# EIT_Teensy_Teensy3_6.net
KiCad netlist of a schematic drawn in Altium Designer
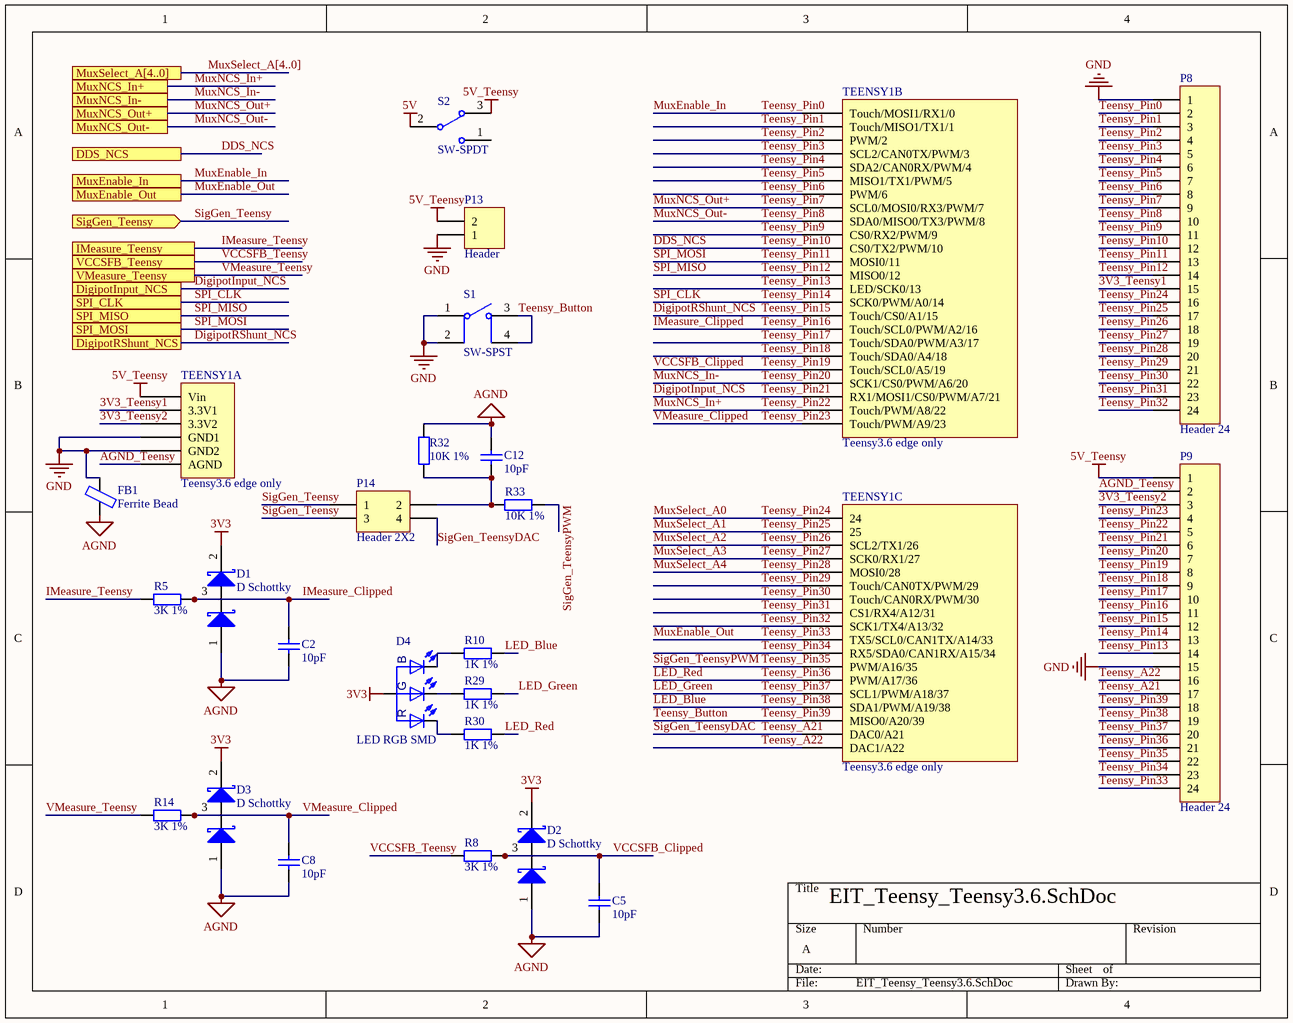
[diagram p0: EIT_Teensy_Teensy3.6.SchDoc]

(export (version "E")
  (design (tool "Eeschema 10.0.6"))
  (components
    (comp (ref "C2")
      (value "10pF")
      (footprint "0603 CAP")
      (fields
        (field (name "MANUFACTURER") "Yageo")
        (field (name "MANUFACTURER PART NUMBER") "CC0603JRNPO9BN100")
        (field (name "TOLERANCE") "5%")
      )
      (libsource (lib "EitLib") (part "Cap 0603 10pF 5% 100V"))
    )
    (comp (ref "C5")
      (value "10pF")
      (footprint "0603 CAP")
      (fields
        (field (name "MANUFACTURER") "Yageo")
        (field (name "MANUFACTURER PART NUMBER") "CC0603JRNPO9BN100")
        (field (name "TOLERANCE") "5%")
      )
      (libsource (lib "EitLib") (part "Cap 0603 10pF 5% 100V"))
    )
    (comp (ref "C8")
      (value "10pF")
      (footprint "0603 CAP")
      (fields
        (field (name "MANUFACTURER") "Yageo")
        (field (name "MANUFACTURER PART NUMBER") "CC0603JRNPO9BN100")
        (field (name "TOLERANCE") "5%")
      )
      (libsource (lib "EitLib") (part "Cap 0603 10pF 5% 100V"))
    )
    (comp (ref "C12")
      (value "10pF")
      (footprint "0603 CAP")
      (fields
        (field (name "MANUFACTURER") "Yageo")
        (field (name "MANUFACTURER PART NUMBER") "CC0603JRNPO9BN100")
        (field (name "TOLERANCE") "5%")
      )
      (libsource (lib "EitLib") (part "Cap 0603 10pF 5% 100V"))
    )
    (comp (ref "D1")
      (value "D Schottky")
      (footprint "SOT-23_STM-M")
      (description "Rectifier Diode Small Signal Schottky 40V 0.3A 5ns 3-Pin SOT-23 T/R")
      (fields
        (field (name "MANUFACTURER") "STMicroelectronics")
        (field (name "MANUFACTURER PART NUMBER") "BAT54SFILM")
      )
      (libsource (lib "EitLib") (part "Diode Array Schottky BAT54S SOT23-3"))
    )
    (comp (ref "D2")
      (value "D Schottky")
      (footprint "SOT-23_STM-M")
      (description "Rectifier Diode Small Signal Schottky 40V 0.3A 5ns 3-Pin SOT-23 T/R")
      (fields
        (field (name "MANUFACTURER") "STMicroelectronics")
        (field (name "MANUFACTURER PART NUMBER") "BAT54SFILM")
      )
      (libsource (lib "EitLib") (part "Diode Array Schottky BAT54S SOT23-3"))
    )
    (comp (ref "D3")
      (value "D Schottky")
      (footprint "SOT-23_STM-M")
      (description "Rectifier Diode Small Signal Schottky 40V 0.3A 5ns 3-Pin SOT-23 T/R")
      (fields
        (field (name "MANUFACTURER") "STMicroelectronics")
        (field (name "MANUFACTURER PART NUMBER") "BAT54SFILM")
      )
      (libsource (lib "EitLib") (part "Diode Array Schottky BAT54S SOT23-3"))
    )
    (comp (ref "D4")
      (value "LED RGB SMD")
      (footprint "LED_RGB")
      (description "LED RGB DIFFUSED SMD")
      (fields
        (field (name "MANUFACTURER") "Wurth Electronics")
        (field (name "MANUFACTURER PART NUMBER") "150066M153000")
      )
      (libsource (lib "EitLib") (part "LED RGB SMD"))
    )
    (comp (ref "FB1")
      (value "Ferrite Bead")
      (footprint "0603 CAP")
      (fields
        (field (name "MANUFACTURER") "Wurth Electronics")
        (field (name "MANUFACTURER PART NUMBER") "742792651")
        (field (name "TOLERANCE") "25%")
      )
      (libsource (lib "EitLib") (part "Ferrite Bead 0603 600R"))
    )
    (comp (ref "P8")
      (value "Header 24")
      (footprint "HDR1X24")
      (description "CONN HEADER .100 SNGL STR 24POS")
      (fields
        (field (name "MANUFACTURER") "Sullins")
        (field (name "MANUFACTURER PART NUMBER") "PRPC024SFAN-RC")
      )
      (libsource (lib "EitLib") (part "Header 24x1 Male"))
    )
    (comp (ref "P9")
      (value "Header 24")
      (footprint "HDR1X24")
      (description "CONN HEADER .100 SNGL STR 24POS")
      (fields
        (field (name "MANUFACTURER") "Sullins")
        (field (name "MANUFACTURER PART NUMBER") "PRPC024SFAN-RC")
      )
      (libsource (lib "EitLib") (part "Header 24x1 Male"))
    )
    (comp (ref "P13")
      (value "Header")
      (footprint "HEADER 2.54MM 2X1 MALE")
      (description "CONN HEADER VERT 2POS 2.54MM")
      (fields
        (field (name "MANUFACTURER") "Sullins")
        (field (name "MANUFACTURER PART NUMBER") "PRPC002SAAN-RC")
      )
      (libsource (lib "EitLib") (part "Header 2x1 2.54mm T/H Male"))
    )
    (comp (ref "P14")
      (value "Header 2X2")
      (footprint "HDR2X2 Male 2.54mm")
      (description "Header, 2-Pin, Dual row")
      (libsource (lib "EitLib") (part "Header 2X2 2.54mm Male"))
    )
    (comp (ref "R5")
      (value "3K 1%")
      (footprint "0603 RES")
      (description "Res Thick Film 0603 3K Ohm 1% 0.1W(1/10W) ±100ppm/C Pad SMD T/R")
      (fields
        (field (name "MANUFACTURER") "Yageo")
        (field (name "MANUFACTURER PART NUMBER") "RC0603FR-073KL")
      )
      (libsource (lib "EitLib") (part "Res 0603 3K 1%"))
    )
    (comp (ref "R8")
      (value "3K 1%")
      (footprint "0603 RES")
      (description "Res Thick Film 0603 3K Ohm 1% 0.1W(1/10W) ±100ppm/C Pad SMD T/R")
      (fields
        (field (name "MANUFACTURER") "Yageo")
        (field (name "MANUFACTURER PART NUMBER") "RC0603FR-073KL")
      )
      (libsource (lib "EitLib") (part "Res 0603 3K 1%"))
    )
    (comp (ref "R10")
      (value "1K 1%")
      (footprint "0603 RES")
      (description "RES SMD 1K OHM 1% 1/10W 0603")
      (fields
        (field (name "MANUFACTURER") "Yageo")
        (field (name "MANUFACTURER PART NUMBER") "RC0603FR-071KL")
      )
      (libsource (lib "EitLib") (part "Res 0603 1K 1%"))
    )
    (comp (ref "R14")
      (value "3K 1%")
      (footprint "0603 RES")
      (description "Res Thick Film 0603 3K Ohm 1% 0.1W(1/10W) ±100ppm/C Pad SMD T/R")
      (fields
        (field (name "MANUFACTURER") "Yageo")
        (field (name "MANUFACTURER PART NUMBER") "RC0603FR-073KL")
      )
      (libsource (lib "EitLib") (part "Res 0603 3K 1%"))
    )
    (comp (ref "R29")
      (value "1K 1%")
      (footprint "0603 RES")
      (description "RES SMD 1K OHM 1% 1/10W 0603")
      (fields
        (field (name "MANUFACTURER") "Yageo")
        (field (name "MANUFACTURER PART NUMBER") "RC0603FR-071KL")
      )
      (libsource (lib "EitLib") (part "Res 0603 1K 1%"))
    )
    (comp (ref "R30")
      (value "1K 1%")
      (footprint "0603 RES")
      (description "RES SMD 1K OHM 1% 1/10W 0603")
      (fields
        (field (name "MANUFACTURER") "Yageo")
        (field (name "MANUFACTURER PART NUMBER") "RC0603FR-071KL")
      )
      (libsource (lib "EitLib") (part "Res 0603 1K 1%"))
    )
    (comp (ref "R32")
      (value "10K 1%")
      (footprint "0603 RES")
      (description "Res General Purpose Thick Film 0603 10K Ohm 1% 1/10W ±100ppm/°C Molded SMD Paper T/R")
      (fields
        (field (name "MANUFACTURER") "Yageo")
        (field (name "MANUFACTURER PART NUMBER") "RC0603FR-0710KL")
      )
      (libsource (lib "") (part "Res 0603 10K 1%_1"))
    )
    (comp (ref "R33")
      (value "10K 1%")
      (footprint "0603 RES")
      (description "Res General Purpose Thick Film 0603 10K Ohm 1% 1/10W ±100ppm/°C Molded SMD Paper T/R")
      (fields
        (field (name "MANUFACTURER") "Yageo")
        (field (name "MANUFACTURER PART NUMBER") "RC0603FR-0710KL")
      )
      (libsource (lib "EitLib") (part "Res 0603 10K 1%"))
    )
    (comp (ref "S1")
      (value "SW-SPST")
      (footprint "Tactile Switch SMD MOM")
      (description "Switch Tactile N.O. SPST Round Button Gull Wing 0.05A 12VDC 2.55N SMD T/R")
      (fields
        (field (name "MANUFACTURER") "E-Switch")
        (field (name "MANUFACTURER PART NUMBER") "TL3305BF260QG")
      )
      (libsource (lib "EitLib") (part "Switch Tactile SMD MOM-NO 50mA"))
    )
    (comp (ref "S2")
      (value "SW-SPDT")
      (footprint "Switch Slide SPDT")
      (description "SWITCH SLIDE SPDT 300MA 125V")
      (fields
        (field (name "MANUFACTURER") "TE Connectivity Alcoswitch")
        (field (name "MANUFACTURER PART NUMBER") "1825255-1")
      )
      (libsource (lib "EitLib") (part "Switch Slide SPDT T/H"))
    )
    (comp (ref "TEENSY1")
      (value "Teensy3.6 edge only")
      (footprint "Teensy3.6-edgeonly")
      (libsource (lib "EitLib") (part "Teensy3.6 edge only"))
    )
  )
  (nets
    (net (code "1") (name "/3V3_Teensy1") (class "Default")
      (node (ref "P8") (pin "15") (pinfunction "15_15") (pintype "passive"))
      (node (ref "TEENSY1") (pin "3.3V1") (pinfunction "3.3V1_3.3V1") (pintype "power_in"))
    )
    (net (code "2") (name "/3V3_Teensy2") (class "Default")
      (node (ref "P9") (pin "3") (pinfunction "3_3") (pintype "passive"))
      (node (ref "TEENSY1") (pin "3.3V2") (pinfunction "3.3V2_3.3V2") (pintype "power_in"))
    )
    (net (code "3") (name "/AGND_Teensy") (class "Default")
      (node (ref "P9") (pin "2") (pinfunction "2_2") (pintype "passive"))
      (node (ref "TEENSY1") (pin "AGND") (pinfunction "AGND_AGND") (pintype "power_in"))
    )
    (net (code "4") (name "/DDS_NCS") (class "Default")
      (node (ref "P8") (pin "12") (pinfunction "12_12") (pintype "passive"))
      (node (ref "TEENSY1") (pin "10") (pinfunction "CS0/TX2/PWM/10_10") (pintype "passive"))
    )
    (net (code "5") (name "/DigipotInput_NCS") (class "Default")
      (node (ref "P9") (pin "6") (pinfunction "6_6") (pintype "passive"))
      (node (ref "TEENSY1") (pin "21") (pinfunction "RX1/MOSI1/CS0/PWM/A7/21_21") (pintype "passive"))
    )
    (net (code "6") (name "/DigipotRShunt_NCS") (class "Default")
      (node (ref "P9") (pin "12") (pinfunction "12_12") (pintype "passive"))
      (node (ref "TEENSY1") (pin "15") (pinfunction "Touch/CS0/A1/15_15") (pintype "passive"))
    )
    (net (code "7") (name "/IMeasure_Clipped") (class "Default")
      (node (ref "C2") (pin "1") (pinfunction "1_1") (pintype "passive"))
      (node (ref "D1") (pin "3") (pinfunction "C_3") (pintype "passive"))
      (node (ref "P9") (pin "11") (pinfunction "11_11") (pintype "passive"))
      (node (ref "R5") (pin "2") (pinfunction "2_2") (pintype "passive"))
      (node (ref "TEENSY1") (pin "16") (pinfunction "Touch/SCL0/PWM/A2/16_16") (pintype "passive"))
    )
    (net (code "8") (name "/IMeasure_Teensy") (class "Default")
      (node (ref "R5") (pin "1") (pinfunction "1_1") (pintype "passive"))
    )
    (net (code "9") (name "/LED_Blue") (class "Default")
      (node (ref "P9") (pin "19") (pinfunction "19_19") (pintype "passive"))
      (node (ref "R10") (pin "1") (pinfunction "1_1") (pintype "passive"))
      (node (ref "TEENSY1") (pin "38") (pinfunction "SDA1/PWM/A19/38_38") (pintype "passive"))
    )
    (net (code "10") (name "/LED_Green") (class "Default")
      (node (ref "P9") (pin "20") (pinfunction "20_20") (pintype "passive"))
      (node (ref "R29") (pin "1") (pinfunction "1_1") (pintype "passive"))
      (node (ref "TEENSY1") (pin "37") (pinfunction "SCL1/PWM/A18/37_37") (pintype "passive"))
    )
    (net (code "11") (name "/LED_Red") (class "Default")
      (node (ref "P9") (pin "21") (pinfunction "21_21") (pintype "passive"))
      (node (ref "R30") (pin "1") (pinfunction "1_1") (pintype "passive"))
      (node (ref "TEENSY1") (pin "36") (pinfunction "PWM/A17/36_36") (pintype "passive"))
    )
    (net (code "12") (name "/MuxEnable_In") (class "Default")
      (node (ref "P8") (pin "2") (pinfunction "2_2") (pintype "passive"))
      (node (ref "TEENSY1") (pin "0") (pinfunction "Touch/MOSI1/RX1/0_0") (pintype "passive"))
    )
    (net (code "13") (name "/MuxEnable_Out") (class "Default")
      (node (ref "P9") (pin "24") (pinfunction "24_24") (pintype "passive"))
      (node (ref "TEENSY1") (pin "33") (pinfunction "TX5/SCL0/CAN1TX/A14/33_33") (pintype "passive"))
    )
    (net (code "14") (name "/MuxNCS_In+") (class "Default")
      (node (ref "P9") (pin "5") (pinfunction "5_5") (pintype "passive"))
      (node (ref "TEENSY1") (pin "22") (pinfunction "Touch/PWM/A8/22_22") (pintype "passive"))
    )
    (net (code "15") (name "/MuxNCS_In-") (class "Default")
      (node (ref "P9") (pin "7") (pinfunction "7_7") (pintype "passive"))
      (node (ref "TEENSY1") (pin "20") (pinfunction "SCK1/CS0/PWM/A6/20_20") (pintype "passive"))
    )
    (net (code "16") (name "/MuxNCS_Out+") (class "Default")
      (node (ref "P8") (pin "9") (pinfunction "9_9") (pintype "passive"))
      (node (ref "TEENSY1") (pin "7") (pinfunction "SCL0/MOSI0/RX3/PWM/7_7") (pintype "passive"))
    )
    (net (code "17") (name "/MuxNCS_Out-") (class "Default")
      (node (ref "P8") (pin "10") (pinfunction "10_10") (pintype "passive"))
      (node (ref "TEENSY1") (pin "8") (pinfunction "SDA0/MISO0/TX3/PWM/8_8") (pintype "passive"))
    )
    (net (code "18") (name "/MuxSelect_A0") (class "Default")
      (node (ref "P8") (pin "16") (pinfunction "16_16") (pintype "passive"))
      (node (ref "TEENSY1") (pin "24") (pinfunction "24_24") (pintype "passive"))
    )
    (net (code "19") (name "/MuxSelect_A1") (class "Default")
      (node (ref "P8") (pin "17") (pinfunction "17_17") (pintype "passive"))
      (node (ref "TEENSY1") (pin "25") (pinfunction "25_25") (pintype "passive"))
    )
    (net (code "20") (name "/MuxSelect_A2") (class "Default")
      (node (ref "P8") (pin "18") (pinfunction "18_18") (pintype "passive"))
      (node (ref "TEENSY1") (pin "26") (pinfunction "SCL2/TX1/26_26") (pintype "passive"))
    )
    (net (code "21") (name "/MuxSelect_A3") (class "Default")
      (node (ref "P8") (pin "19") (pinfunction "19_19") (pintype "passive"))
      (node (ref "TEENSY1") (pin "27") (pinfunction "SCK0/RX1/27_27") (pintype "passive"))
    )
    (net (code "22") (name "/MuxSelect_A4") (class "Default")
      (node (ref "P8") (pin "20") (pinfunction "20_20") (pintype "passive"))
      (node (ref "TEENSY1") (pin "28") (pinfunction "MOSI0/28_28") (pintype "passive"))
    )
    (net (code "24") (name "/SPI_CLK") (class "Default")
      (node (ref "P9") (pin "13") (pinfunction "13_13") (pintype "passive"))
      (node (ref "TEENSY1") (pin "14") (pinfunction "SCK0/PWM/A0/14_14") (pintype "passive"))
    )
    (net (code "25") (name "/SPI_MISO") (class "Default")
      (node (ref "P8") (pin "14") (pinfunction "14_14") (pintype "passive"))
      (node (ref "TEENSY1") (pin "12") (pinfunction "MISO0/12_12") (pintype "passive"))
    )
    (net (code "26") (name "/SPI_MOSI") (class "Default")
      (node (ref "P8") (pin "13") (pinfunction "13_13") (pintype "passive"))
      (node (ref "TEENSY1") (pin "11") (pinfunction "MOSI0/11_11") (pintype "passive"))
    )
    (net (code "27") (name "/SigGen_Teensy") (class "Default")
      (node (ref "P14") (pin "1") (pinfunction "1_1") (pintype "passive"))
      (node (ref "P14") (pin "3") (pinfunction "3_3") (pintype "passive"))
    )
    (net (code "28") (name "/SigGen_TeensyDAC") (class "Default")
      (node (ref "P14") (pin "4") (pinfunction "4_4") (pintype "passive"))
      (node (ref "P9") (pin "17") (pinfunction "17_17") (pintype "passive"))
      (node (ref "TEENSY1") (pin "A21") (pinfunction "DAC0/A21_A21") (pintype "passive"))
    )
    (net (code "29") (name "/SigGen_TeensyPWM") (class "Default")
      (node (ref "P9") (pin "22") (pinfunction "22_22") (pintype "passive"))
      (node (ref "R33") (pin "1") (pinfunction "1_1") (pintype "passive"))
      (node (ref "TEENSY1") (pin "35") (pinfunction "PWM/A16/35_35") (pintype "passive"))
    )
    (net (code "30") (name "/Teensy_A22") (class "Default")
      (node (ref "P9") (pin "16") (pinfunction "16_16") (pintype "passive"))
      (node (ref "TEENSY1") (pin "A22") (pinfunction "DAC1/A22_A22") (pintype "passive"))
    )
    (net (code "31") (name "/Teensy_Button") (class "Default")
      (node (ref "P9") (pin "18") (pinfunction "18_18") (pintype "passive"))
      (node (ref "S1") (pin "3") (pinfunction "COMMON_3") (pintype "passive"))
      (node (ref "S1") (pin "4") (pinfunction "NO_4") (pintype "passive"))
      (node (ref "TEENSY1") (pin "39") (pinfunction "MISO0/A20/39_39") (pintype "passive"))
    )
    (net (code "32") (name "/Teensy_Pin1") (class "Default")
      (node (ref "P8") (pin "3") (pinfunction "3_3") (pintype "passive"))
      (node (ref "TEENSY1") (pin "1") (pinfunction "Touch/MISO1/TX1/1_1") (pintype "passive"))
    )
    (net (code "33") (name "/Teensy_Pin2") (class "Default")
      (node (ref "P8") (pin "4") (pinfunction "4_4") (pintype "passive"))
      (node (ref "TEENSY1") (pin "2") (pinfunction "PWM/2_2") (pintype "passive"))
    )
    (net (code "34") (name "/Teensy_Pin3") (class "Default")
      (node (ref "P8") (pin "5") (pinfunction "5_5") (pintype "passive"))
      (node (ref "TEENSY1") (pin "3") (pinfunction "SCL2/CAN0TX/PWM/3_3") (pintype "passive"))
    )
    (net (code "35") (name "/Teensy_Pin4") (class "Default")
      (node (ref "P8") (pin "6") (pinfunction "6_6") (pintype "passive"))
      (node (ref "TEENSY1") (pin "4") (pinfunction "SDA2/CAN0RX/PWM/4_4") (pintype "passive"))
    )
    (net (code "36") (name "/Teensy_Pin5") (class "Default")
      (node (ref "P8") (pin "7") (pinfunction "7_7") (pintype "passive"))
      (node (ref "TEENSY1") (pin "5") (pinfunction "MISO1/TX1/PWM/5_5") (pintype "passive"))
    )
    (net (code "37") (name "/Teensy_Pin6") (class "Default")
      (node (ref "P8") (pin "8") (pinfunction "8_8") (pintype "passive"))
      (node (ref "TEENSY1") (pin "6") (pinfunction "PWM/6_6") (pintype "passive"))
    )
    (net (code "38") (name "/Teensy_Pin9") (class "Default")
      (node (ref "P8") (pin "11") (pinfunction "11_11") (pintype "passive"))
      (node (ref "TEENSY1") (pin "9") (pinfunction "CS0/RX2/PWM/9_9") (pintype "passive"))
    )
    (net (code "39") (name "/Teensy_Pin13") (class "Default")
      (node (ref "P9") (pin "14") (pinfunction "14_14") (pintype "passive"))
      (node (ref "TEENSY1") (pin "13") (pinfunction "LED/SCK0/13_13") (pintype "passive"))
    )
    (net (code "40") (name "/Teensy_Pin17") (class "Default")
      (node (ref "P9") (pin "10") (pinfunction "10_10") (pintype "passive"))
      (node (ref "TEENSY1") (pin "17") (pinfunction "Touch/SDA0/PWM/A3/17_17") (pintype "passive"))
    )
    (net (code "41") (name "/Teensy_Pin18") (class "Default")
      (node (ref "P9") (pin "9") (pinfunction "9_9") (pintype "passive"))
      (node (ref "TEENSY1") (pin "18") (pinfunction "Touch/SDA0/A4/18_18") (pintype "passive"))
    )
    (net (code "42") (name "/Teensy_Pin19") (class "Default")
      (node (ref "C5") (pin "1") (pinfunction "1_1") (pintype "passive"))
      (node (ref "D2") (pin "3") (pinfunction "C_3") (pintype "passive"))
      (node (ref "P9") (pin "8") (pinfunction "8_8") (pintype "passive"))
      (node (ref "R8") (pin "2") (pinfunction "2_2") (pintype "passive"))
      (node (ref "TEENSY1") (pin "19") (pinfunction "Touch/SCL0/A5/19_19") (pintype "passive"))
    )
    (net (code "43") (name "/Teensy_Pin23") (class "Default")
      (node (ref "C8") (pin "1") (pinfunction "1_1") (pintype "passive"))
      (node (ref "D3") (pin "3") (pinfunction "C_3") (pintype "passive"))
      (node (ref "P9") (pin "4") (pinfunction "4_4") (pintype "passive"))
      (node (ref "R14") (pin "2") (pinfunction "2_2") (pintype "passive"))
      (node (ref "TEENSY1") (pin "23") (pinfunction "Touch/PWM/A9/23_23") (pintype "passive"))
    )
    (net (code "44") (name "/Teensy_Pin29") (class "Default")
      (node (ref "P8") (pin "21") (pinfunction "21_21") (pintype "passive"))
      (node (ref "TEENSY1") (pin "29") (pinfunction "Touch/CAN0TX/PWM/29_29") (pintype "passive"))
    )
    (net (code "45") (name "/Teensy_Pin30") (class "Default")
      (node (ref "P8") (pin "22") (pinfunction "22_22") (pintype "passive"))
      (node (ref "TEENSY1") (pin "30") (pinfunction "Touch/CAN0RX/PWM/30_30") (pintype "passive"))
    )
    (net (code "46") (name "/Teensy_Pin31") (class "Default")
      (node (ref "P8") (pin "23") (pinfunction "23_23") (pintype "passive"))
      (node (ref "TEENSY1") (pin "31") (pinfunction "CS1/RX4/A12/31_31") (pintype "passive"))
    )
    (net (code "47") (name "/Teensy_Pin32") (class "Default")
      (node (ref "P8") (pin "24") (pinfunction "24_24") (pintype "passive"))
      (node (ref "TEENSY1") (pin "32") (pinfunction "SCK1/TX4/A13/32_32") (pintype "passive"))
    )
    (net (code "48") (name "/Teensy_Pin34") (class "Default")
      (node (ref "P9") (pin "23") (pinfunction "23_23") (pintype "passive"))
      (node (ref "TEENSY1") (pin "34") (pinfunction "RX5/SDA0/CAN1RX/A15/34_34") (pintype "passive"))
    )
    (net (code "49") (name "/VCCSFB_Teensy") (class "Default")
      (node (ref "R8") (pin "1") (pinfunction "1_1") (pintype "passive"))
    )
    (net (code "50") (name "/VMeasure_Teensy") (class "Default")
      (node (ref "R14") (pin "1") (pinfunction "1_1") (pintype "passive"))
    )
    (net (code "51") (name "3V3") (class "Default")
      (node (ref "D1") (pin "2") (pinfunction "K_2") (pintype "passive"))
      (node (ref "D2") (pin "2") (pinfunction "K_2") (pintype "passive"))
      (node (ref "D3") (pin "2") (pinfunction "K_2") (pintype "passive"))
      (node (ref "D4") (pin "4") (pinfunction "CA_4") (pintype "passive"))
    )
    (net (code "52") (name "5V") (class "Default")
      (node (ref "S2") (pin "2") (pinfunction "2_2") (pintype "passive"))
    )
    (net (code "53") (name "5V_Teensy") (class "Default")
      (node (ref "P13") (pin "2") (pinfunction "2_2") (pintype "passive"))
      (node (ref "P9") (pin "1") (pinfunction "1_1") (pintype "passive"))
      (node (ref "S2") (pin "3") (pinfunction "3_3") (pintype "passive"))
      (node (ref "TEENSY1") (pin "VIN") (pinfunction "Vin_VIN") (pintype "power_in"))
    )
    (net (code "54") (name "AGND") (class "Default")
      (node (ref "C12") (pin "1") (pinfunction "1_1") (pintype "passive"))
      (node (ref "C2") (pin "2") (pinfunction "2_2") (pintype "passive"))
      (node (ref "C5") (pin "2") (pinfunction "2_2") (pintype "passive"))
      (node (ref "C8") (pin "2") (pinfunction "2_2") (pintype "passive"))
      (node (ref "D1") (pin "1") (pinfunction "A_1") (pintype "passive"))
      (node (ref "D2") (pin "1") (pinfunction "A_1") (pintype "passive"))
      (node (ref "D3") (pin "1") (pinfunction "A_1") (pintype "passive"))
      (node (ref "FB1") (pin "1") (pinfunction "1_1") (pintype "passive"))
      (node (ref "R32") (pin "2") (pinfunction "2_2") (pintype "passive"))
    )
    (net (code "55") (name "GND") (class "Default")
      (node (ref "FB1") (pin "2") (pinfunction "2_2") (pintype "passive"))
      (node (ref "P13") (pin "1") (pinfunction "1_1") (pintype "passive"))
      (node (ref "P8") (pin "1") (pinfunction "1_1") (pintype "passive"))
      (node (ref "P9") (pin "15") (pinfunction "15_15") (pintype "passive"))
      (node (ref "S1") (pin "1") (pinfunction "COMMON_1") (pintype "passive"))
      (node (ref "S1") (pin "2") (pinfunction "NO_2") (pintype "passive"))
      (node (ref "TEENSY1") (pin "GND1") (pinfunction "GND1_GND1") (pintype "power_in"))
      (node (ref "TEENSY1") (pin "GND2") (pinfunction "GND2_GND2") (pintype "power_in"))
    )
    (net (code "56") (name "Net-(C12-Pad2)") (class "Default")
      (node (ref "C12") (pin "2") (pinfunction "2_2") (pintype "passive"))
      (node (ref "P14") (pin "2") (pinfunction "2_2") (pintype "passive"))
      (node (ref "R32") (pin "1") (pinfunction "1_1") (pintype "passive"))
      (node (ref "R33") (pin "2") (pinfunction "2_2") (pintype "passive"))
    )
    (net (code "57") (name "Net-(D4-B)") (class "Default")
      (node (ref "D4") (pin "3") (pinfunction "B_3") (pintype "passive"))
      (node (ref "R10") (pin "2") (pinfunction "2_2") (pintype "passive"))
    )
    (net (code "58") (name "Net-(D4-G)") (class "Default")
      (node (ref "D4") (pin "2") (pinfunction "G_2") (pintype "passive"))
      (node (ref "R29") (pin "2") (pinfunction "2_2") (pintype "passive"))
    )
    (net (code "59") (name "Net-(D4-R)") (class "Default")
      (node (ref "D4") (pin "1") (pinfunction "R_1") (pintype "passive"))
      (node (ref "R30") (pin "2") (pinfunction "2_2") (pintype "passive"))
    )
    (net (code "60") (name "unconnected-(S2-Pad1)") (class "Default")
      (node (ref "S2") (pin "1") (pinfunction "1_1") (pintype "passive"))
    )
  )
)
